# design.net
KiCad netlist of a schematic drawn in Altium Designer
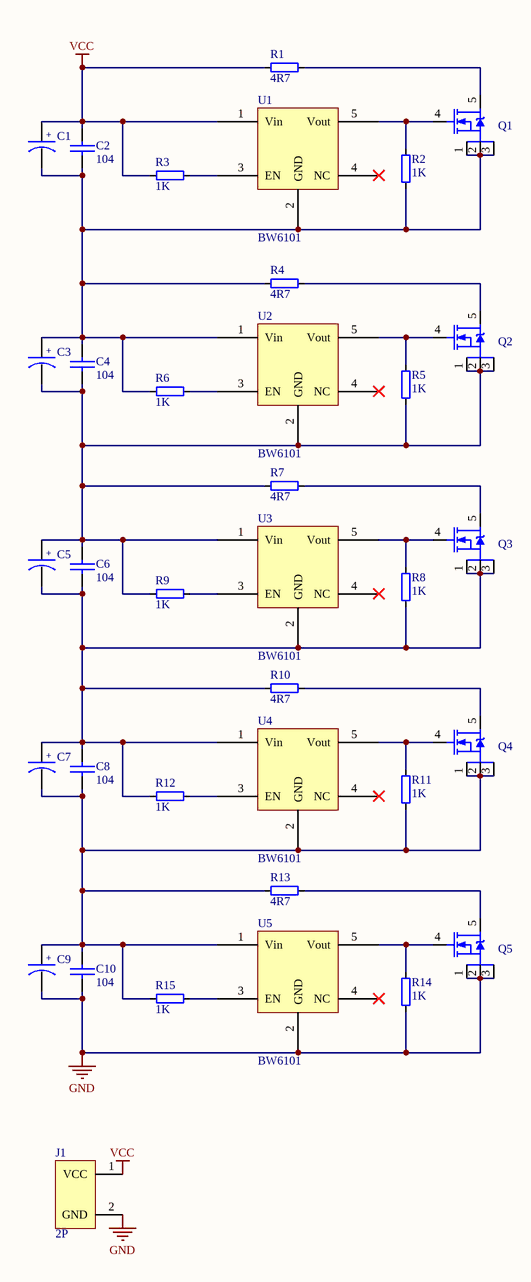
[diagram p0: 超级电容.SchDoc]

(export (version "E")
  (design (tool "Eeschema 10.0.6"))
  (components
    (comp (ref "C1") (value "BCAP0025") (footprint "BCAP0025") (libsource (lib "MyLib") (part "BCAP0025")))
    (comp (ref "C2") (value "104") (footprint "C0603") (libsource (lib "MyLib") (part "MLCC")))
    (comp (ref "C3") (value "BCAP0025") (footprint "BCAP0025") (libsource (lib "MyLib") (part "BCAP0025")))
    (comp (ref "C4") (value "104") (footprint "C0603") (libsource (lib "MyLib") (part "MLCC")))
    (comp (ref "C5") (value "BCAP0025") (footprint "BCAP0025") (libsource (lib "MyLib") (part "BCAP0025")))
    (comp (ref "C6") (value "104") (footprint "C0603") (libsource (lib "MyLib") (part "MLCC")))
    (comp (ref "C7") (value "BCAP0025") (footprint "BCAP0025") (libsource (lib "MyLib") (part "BCAP0025")))
    (comp (ref "C8") (value "104") (footprint "C0603") (libsource (lib "MyLib") (part "MLCC")))
    (comp (ref "C9") (value "BCAP0025") (footprint "BCAP0025") (libsource (lib "MyLib") (part "BCAP0025")))
    (comp (ref "C10") (value "104") (footprint "C0603") (libsource (lib "MyLib") (part "MLCC")))
    (comp (ref "J1") (value "2P") (footprint "XT30母") (libsource (lib "MyLib") (part "2P")))
    (comp (ref "Q1")
      (value "PSMN1R4-40YLD")
      (footprint "PSMN1R4-40YLD")
      (libsource (lib "MyLib") (part "PSMN1R4-40YLD"))
    )
    (comp (ref "Q2")
      (value "PSMN1R4-40YLD")
      (footprint "PSMN1R4-40YLD")
      (libsource (lib "MyLib") (part "PSMN1R4-40YLD"))
    )
    (comp (ref "Q3")
      (value "PSMN1R4-40YLD")
      (footprint "PSMN1R4-40YLD")
      (libsource (lib "MyLib") (part "PSMN1R4-40YLD"))
    )
    (comp (ref "Q4")
      (value "PSMN1R4-40YLD")
      (footprint "PSMN1R4-40YLD")
      (libsource (lib "MyLib") (part "PSMN1R4-40YLD"))
    )
    (comp (ref "Q5")
      (value "PSMN1R4-40YLD")
      (footprint "PSMN1R4-40YLD")
      (libsource (lib "MyLib") (part "PSMN1R4-40YLD"))
    )
    (comp (ref "R1") (value "4R7") (footprint "R2512") (libsource (lib "MyLib") (part "RES")))
    (comp (ref "R2") (value "1K") (footprint "R0603") (libsource (lib "MyLib") (part "RES")))
    (comp (ref "R3") (value "1K") (footprint "R0603") (libsource (lib "MyLib") (part "RES")))
    (comp (ref "R4") (value "4R7") (footprint "R2512") (libsource (lib "MyLib") (part "RES")))
    (comp (ref "R5") (value "1K") (footprint "R0603") (libsource (lib "MyLib") (part "RES")))
    (comp (ref "R6") (value "1K") (footprint "R0603") (libsource (lib "MyLib") (part "RES")))
    (comp (ref "R7") (value "4R7") (footprint "R2512") (libsource (lib "MyLib") (part "RES")))
    (comp (ref "R8") (value "1K") (footprint "R0603") (libsource (lib "MyLib") (part "RES")))
    (comp (ref "R9") (value "1K") (footprint "R0603") (libsource (lib "MyLib") (part "RES")))
    (comp (ref "R10") (value "4R7") (footprint "R2512") (libsource (lib "MyLib") (part "RES")))
    (comp (ref "R11") (value "1K") (footprint "R0603") (libsource (lib "MyLib") (part "RES")))
    (comp (ref "R12") (value "1K") (footprint "R0603") (libsource (lib "MyLib") (part "RES")))
    (comp (ref "R13") (value "4R7") (footprint "R2512") (libsource (lib "MyLib") (part "RES")))
    (comp (ref "R14") (value "1K") (footprint "R0603") (libsource (lib "MyLib") (part "RES")))
    (comp (ref "R15") (value "1K") (footprint "R0603") (libsource (lib "MyLib") (part "RES")))
    (comp (ref "U1") (value "BW6101") (footprint "SOT23-5") (libsource (lib "MyLib") (part "BW6101")))
    (comp (ref "U2") (value "BW6101") (footprint "SOT23-5") (libsource (lib "MyLib") (part "BW6101")))
    (comp (ref "U3") (value "BW6101") (footprint "SOT23-5") (libsource (lib "MyLib") (part "BW6101")))
    (comp (ref "U4") (value "BW6101") (footprint "SOT23-5") (libsource (lib "MyLib") (part "BW6101")))
    (comp (ref "U5") (value "BW6101") (footprint "SOT23-5") (libsource (lib "MyLib") (part "BW6101")))
  )
  (nets
    (net (code "1") (name "GND") (class "Default")
      (node (ref "C10") (pin "2") (pinfunction "2_2") (pintype "passive"))
      (node (ref "C9") (pin "2") (pinfunction "2_2") (pintype "passive"))
      (node (ref "J1") (pin "2") (pinfunction "GND_2") (pintype "passive"))
      (node (ref "Q5") (pin "1") (pinfunction "S_1") (pintype "passive"))
      (node (ref "Q5") (pin "2") (pinfunction "S_2") (pintype "passive"))
      (node (ref "Q5") (pin "3") (pinfunction "S_3") (pintype "passive"))
      (node (ref "R14") (pin "1") (pinfunction "1_1") (pintype "passive"))
      (node (ref "U5") (pin "2") (pinfunction "GND_2") (pintype "passive"))
    )
    (net (code "2") (name "Net-(Q1-D)") (class "Default")
      (node (ref "Q1") (pin "5") (pinfunction "D_5") (pintype "passive"))
      (node (ref "R1") (pin "2") (pinfunction "2_2") (pintype "passive"))
    )
    (net (code "3") (name "Net-(Q1-G)") (class "Default")
      (node (ref "Q1") (pin "4") (pinfunction "G_4") (pintype "passive"))
      (node (ref "R2") (pin "2") (pinfunction "2_2") (pintype "passive"))
      (node (ref "U1") (pin "5") (pinfunction "Vout_5") (pintype "passive"))
    )
    (net (code "4") (name "Net-(Q2-D)") (class "Default")
      (node (ref "Q2") (pin "5") (pinfunction "D_5") (pintype "passive"))
      (node (ref "R4") (pin "2") (pinfunction "2_2") (pintype "passive"))
    )
    (net (code "5") (name "Net-(Q2-G)") (class "Default")
      (node (ref "Q2") (pin "4") (pinfunction "G_4") (pintype "passive"))
      (node (ref "R5") (pin "2") (pinfunction "2_2") (pintype "passive"))
      (node (ref "U2") (pin "5") (pinfunction "Vout_5") (pintype "passive"))
    )
    (net (code "6") (name "Net-(Q3-D)") (class "Default")
      (node (ref "Q3") (pin "5") (pinfunction "D_5") (pintype "passive"))
      (node (ref "R7") (pin "2") (pinfunction "2_2") (pintype "passive"))
    )
    (net (code "7") (name "Net-(Q3-G)") (class "Default")
      (node (ref "Q3") (pin "4") (pinfunction "G_4") (pintype "passive"))
      (node (ref "R8") (pin "2") (pinfunction "2_2") (pintype "passive"))
      (node (ref "U3") (pin "5") (pinfunction "Vout_5") (pintype "passive"))
    )
    (net (code "8") (name "Net-(Q4-D)") (class "Default")
      (node (ref "Q4") (pin "5") (pinfunction "D_5") (pintype "passive"))
      (node (ref "R10") (pin "2") (pinfunction "2_2") (pintype "passive"))
    )
    (net (code "9") (name "Net-(Q4-G)") (class "Default")
      (node (ref "Q4") (pin "4") (pinfunction "G_4") (pintype "passive"))
      (node (ref "R11") (pin "2") (pinfunction "2_2") (pintype "passive"))
      (node (ref "U4") (pin "5") (pinfunction "Vout_5") (pintype "passive"))
    )
    (net (code "10") (name "Net-(Q5-D)") (class "Default")
      (node (ref "Q5") (pin "5") (pinfunction "D_5") (pintype "passive"))
      (node (ref "R13") (pin "2") (pinfunction "2_2") (pintype "passive"))
    )
    (net (code "11") (name "Net-(Q5-G)") (class "Default")
      (node (ref "Q5") (pin "4") (pinfunction "G_4") (pintype "passive"))
      (node (ref "R14") (pin "2") (pinfunction "2_2") (pintype "passive"))
      (node (ref "U5") (pin "5") (pinfunction "Vout_5") (pintype "passive"))
    )
    (net (code "12") (name "Net-(U1-EN)") (class "Default")
      (node (ref "R3") (pin "2") (pinfunction "2_2") (pintype "passive"))
      (node (ref "U1") (pin "3") (pinfunction "EN_3") (pintype "passive"))
    )
    (net (code "13") (name "Net-(U1-GND)") (class "Default")
      (node (ref "C1") (pin "2") (pinfunction "2_2") (pintype "passive"))
      (node (ref "C2") (pin "2") (pinfunction "2_2") (pintype "passive"))
      (node (ref "C3") (pin "1") (pinfunction "1_1") (pintype "passive"))
      (node (ref "C4") (pin "1") (pinfunction "1_1") (pintype "passive"))
      (node (ref "Q1") (pin "1") (pinfunction "S_1") (pintype "passive"))
      (node (ref "Q1") (pin "2") (pinfunction "S_2") (pintype "passive"))
      (node (ref "Q1") (pin "3") (pinfunction "S_3") (pintype "passive"))
      (node (ref "R2") (pin "1") (pinfunction "1_1") (pintype "passive"))
      (node (ref "R4") (pin "1") (pinfunction "1_1") (pintype "passive"))
      (node (ref "R6") (pin "1") (pinfunction "1_1") (pintype "passive"))
      (node (ref "U1") (pin "2") (pinfunction "GND_2") (pintype "passive"))
      (node (ref "U2") (pin "1") (pinfunction "Vin_1") (pintype "passive"))
    )
    (net (code "14") (name "Net-(U2-EN)") (class "Default")
      (node (ref "R6") (pin "2") (pinfunction "2_2") (pintype "passive"))
      (node (ref "U2") (pin "3") (pinfunction "EN_3") (pintype "passive"))
    )
    (net (code "15") (name "Net-(U2-GND)") (class "Default")
      (node (ref "C3") (pin "2") (pinfunction "2_2") (pintype "passive"))
      (node (ref "C4") (pin "2") (pinfunction "2_2") (pintype "passive"))
      (node (ref "C5") (pin "1") (pinfunction "1_1") (pintype "passive"))
      (node (ref "C6") (pin "1") (pinfunction "1_1") (pintype "passive"))
      (node (ref "Q2") (pin "1") (pinfunction "S_1") (pintype "passive"))
      (node (ref "Q2") (pin "2") (pinfunction "S_2") (pintype "passive"))
      (node (ref "Q2") (pin "3") (pinfunction "S_3") (pintype "passive"))
      (node (ref "R5") (pin "1") (pinfunction "1_1") (pintype "passive"))
      (node (ref "R7") (pin "1") (pinfunction "1_1") (pintype "passive"))
      (node (ref "R9") (pin "1") (pinfunction "1_1") (pintype "passive"))
      (node (ref "U2") (pin "2") (pinfunction "GND_2") (pintype "passive"))
      (node (ref "U3") (pin "1") (pinfunction "Vin_1") (pintype "passive"))
    )
    (net (code "16") (name "Net-(U3-EN)") (class "Default")
      (node (ref "R9") (pin "2") (pinfunction "2_2") (pintype "passive"))
      (node (ref "U3") (pin "3") (pinfunction "EN_3") (pintype "passive"))
    )
    (net (code "17") (name "Net-(U3-GND)") (class "Default")
      (node (ref "C5") (pin "2") (pinfunction "2_2") (pintype "passive"))
      (node (ref "C6") (pin "2") (pinfunction "2_2") (pintype "passive"))
      (node (ref "C7") (pin "1") (pinfunction "1_1") (pintype "passive"))
      (node (ref "C8") (pin "1") (pinfunction "1_1") (pintype "passive"))
      (node (ref "Q3") (pin "1") (pinfunction "S_1") (pintype "passive"))
      (node (ref "Q3") (pin "2") (pinfunction "S_2") (pintype "passive"))
      (node (ref "Q3") (pin "3") (pinfunction "S_3") (pintype "passive"))
      (node (ref "R10") (pin "1") (pinfunction "1_1") (pintype "passive"))
      (node (ref "R12") (pin "1") (pinfunction "1_1") (pintype "passive"))
      (node (ref "R8") (pin "1") (pinfunction "1_1") (pintype "passive"))
      (node (ref "U3") (pin "2") (pinfunction "GND_2") (pintype "passive"))
      (node (ref "U4") (pin "1") (pinfunction "Vin_1") (pintype "passive"))
    )
    (net (code "18") (name "Net-(U4-EN)") (class "Default")
      (node (ref "R12") (pin "2") (pinfunction "2_2") (pintype "passive"))
      (node (ref "U4") (pin "3") (pinfunction "EN_3") (pintype "passive"))
    )
    (net (code "19") (name "Net-(U4-GND)") (class "Default")
      (node (ref "C10") (pin "1") (pinfunction "1_1") (pintype "passive"))
      (node (ref "C7") (pin "2") (pinfunction "2_2") (pintype "passive"))
      (node (ref "C8") (pin "2") (pinfunction "2_2") (pintype "passive"))
      (node (ref "C9") (pin "1") (pinfunction "1_1") (pintype "passive"))
      (node (ref "Q4") (pin "1") (pinfunction "S_1") (pintype "passive"))
      (node (ref "Q4") (pin "2") (pinfunction "S_2") (pintype "passive"))
      (node (ref "Q4") (pin "3") (pinfunction "S_3") (pintype "passive"))
      (node (ref "R11") (pin "1") (pinfunction "1_1") (pintype "passive"))
      (node (ref "R13") (pin "1") (pinfunction "1_1") (pintype "passive"))
      (node (ref "R15") (pin "1") (pinfunction "1_1") (pintype "passive"))
      (node (ref "U4") (pin "2") (pinfunction "GND_2") (pintype "passive"))
      (node (ref "U5") (pin "1") (pinfunction "Vin_1") (pintype "passive"))
    )
    (net (code "20") (name "Net-(U5-EN)") (class "Default")
      (node (ref "R15") (pin "2") (pinfunction "2_2") (pintype "passive"))
      (node (ref "U5") (pin "3") (pinfunction "EN_3") (pintype "passive"))
    )
    (net (code "21") (name "VCC") (class "Default")
      (node (ref "C1") (pin "1") (pinfunction "1_1") (pintype "passive"))
      (node (ref "C2") (pin "1") (pinfunction "1_1") (pintype "passive"))
      (node (ref "J1") (pin "1") (pinfunction "VCC_1") (pintype "passive"))
      (node (ref "R1") (pin "1") (pinfunction "1_1") (pintype "passive"))
      (node (ref "R3") (pin "1") (pinfunction "1_1") (pintype "passive"))
      (node (ref "U1") (pin "1") (pinfunction "Vin_1") (pintype "passive"))
    )
    (net (code "22") (name "unconnected-(U1-NC-Pad4)") (class "Default")
      (node (ref "U1") (pin "4") (pinfunction "NC_4") (pintype "passive+no_connect"))
    )
    (net (code "23") (name "unconnected-(U2-NC-Pad4)") (class "Default")
      (node (ref "U2") (pin "4") (pinfunction "NC_4") (pintype "passive+no_connect"))
    )
    (net (code "24") (name "unconnected-(U3-NC-Pad4)") (class "Default")
      (node (ref "U3") (pin "4") (pinfunction "NC_4") (pintype "passive+no_connect"))
    )
    (net (code "25") (name "unconnected-(U4-NC-Pad4)") (class "Default")
      (node (ref "U4") (pin "4") (pinfunction "NC_4") (pintype "passive+no_connect"))
    )
    (net (code "26") (name "unconnected-(U5-NC-Pad4)") (class "Default")
      (node (ref "U5") (pin "4") (pinfunction "NC_4") (pintype "passive+no_connect"))
    )
  )
)
